# Sheet1.net
KiCad netlist of a schematic drawn in Altium Designer
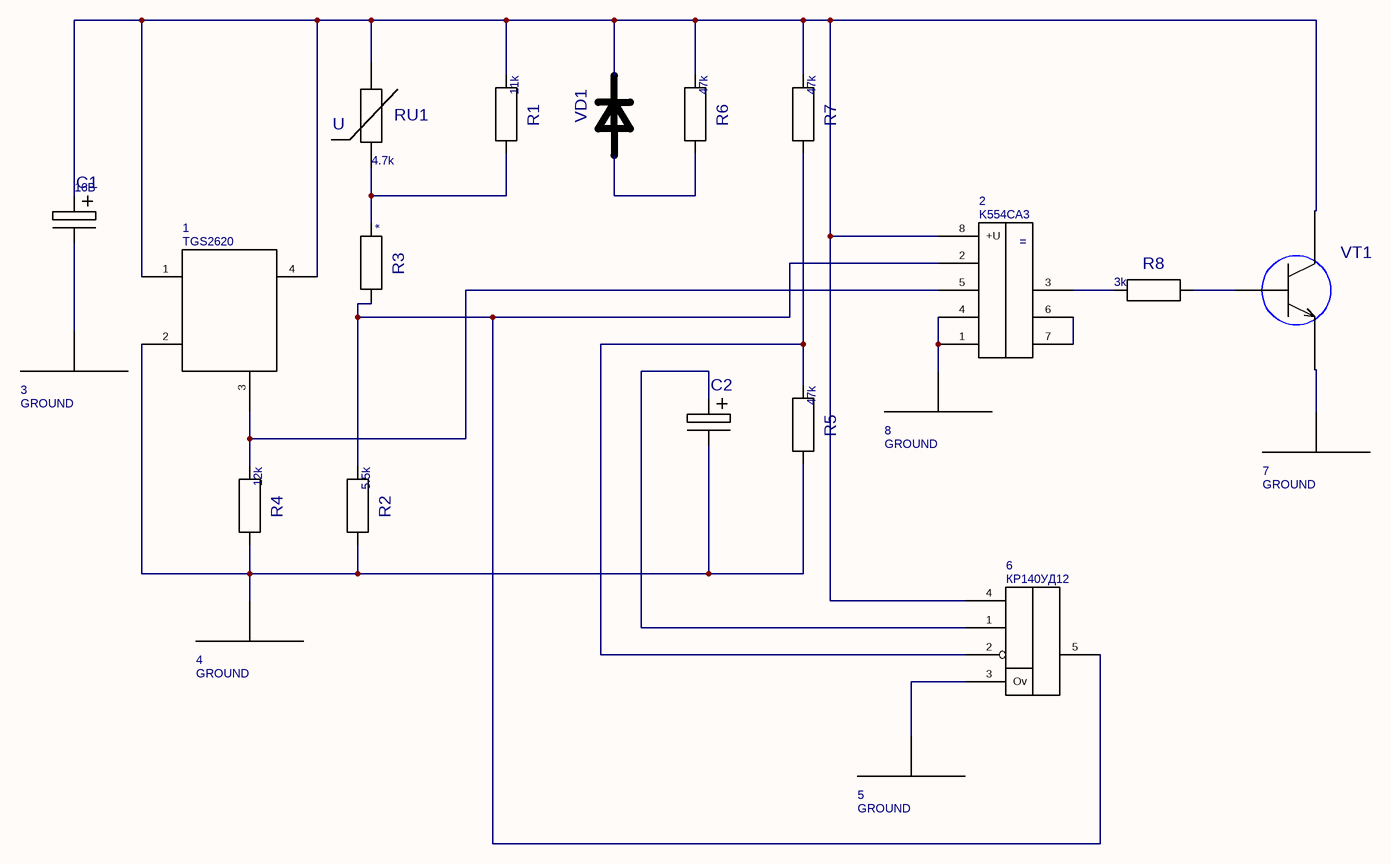
[diagram p0: Sheet1.SCHDOC]

(export (version "E")
  (design (tool "Eeschema 10.0.6"))
  (components
    (comp (ref "1") (value "TGS2620") (footprint "TGS2620") (libsource (lib "*") (part "TGS2620")))
    (comp (ref "2") (value "K554CA3") (footprint "K554CA3") (libsource (lib "*") (part "K554CA3")))
    (comp (ref "3") (value "GROUND") (footprint "GROUND") (libsource (lib "*") (part "GROUND")))
    (comp (ref "4") (value "GROUND") (footprint "GROUND") (libsource (lib "*") (part "GROUND")))
    (comp (ref "5") (value "GROUND") (footprint "GROUND") (libsource (lib "*") (part "GROUND")))
    (comp (ref "6") (value "КР140УД12") (footprint "КР140УД12") (libsource (lib "*") (part "КР140УД12")))
    (comp (ref "7") (value "GROUND") (footprint "GROUND") (libsource (lib "*") (part "GROUND")))
    (comp (ref "8") (value "GROUND") (footprint "GROUND") (libsource (lib "*") (part "GROUND")))
    (comp (ref "C1")
      (value "16B")
      (footprint "R50-35-08XX")
      (description "К50-35-1000МКФ-6,3В")
      (libsource (lib "*") (part "К50-35-1000МКФ-6,3В"))
    )
    (comp (ref "C2")
      (value "К50-35-220МКФ-10В-Г")
      (footprint "К50-35-0611-Г")
      (libsource (lib "*") (part "К50-35-220МКФ-10В-Г"))
    )
    (comp (ref "R1")
      (value "11k")
      (footprint "PR03(VISHAY)")
      (description "PR03(VISHAY)")
      (libsource (lib "*") (part "PR03(VISHAY)"))
    )
    (comp (ref "R2")
      (value "5.5k")
      (footprint "PR03(VISHAY)")
      (description "PR03(VISHAY)")
      (libsource (lib "*") (part "PR03(VISHAY)"))
    )
    (comp (ref "R3")
      (value "PR03(VISHAY)")
      (footprint "PR03(VISHAY)")
      (fields (field (name "ALTIUM_VALUE") "*"))
      (libsource (lib "*") (part "PR03(VISHAY)"))
    )
    (comp (ref "R4")
      (value "12k")
      (footprint "PR03(VISHAY)")
      (description "PR03(VISHAY)")
      (libsource (lib "*") (part "PR03(VISHAY)"))
    )
    (comp (ref "R5")
      (value "47k")
      (footprint "PR03(VISHAY)")
      (description "PR03(VISHAY)")
      (libsource (lib "*") (part "PR03(VISHAY)"))
    )
    (comp (ref "R6")
      (value "47k")
      (footprint "PR03(VISHAY)")
      (description "PR03(VISHAY)")
      (libsource (lib "*") (part "PR03(VISHAY)"))
    )
    (comp (ref "R7")
      (value "47k")
      (footprint "PR03(VISHAY)")
      (description "PR03(VISHAY)")
      (libsource (lib "*") (part "PR03(VISHAY)"))
    )
    (comp (ref "R8")
      (value "3k")
      (footprint "PR03(VISHAY)")
      (description "PR03(VISHAY)")
      (libsource (lib "*") (part "PR03(VISHAY)"))
    )
    (comp (ref "RU1")
      (value "4.7k")
      (footprint "S07K230")
      (description "SIOV-S07K300")
      (fields (field (name "AUTHOR") "pcbdesigner.ru"))
      (libsource (lib "*") (part "SIOV-S07K300"))
    )
    (comp (ref "VD1") (value "1N34") (footprint "DO-7") (libsource (lib "*") (part "1N34")))
    (comp (ref "VT1") (value "2N4401") (footprint "TO-92-1") (libsource (lib "*") (part "2N4401")))
  )
  (nets
    (net (code "1") (name "Net-(1-Pad2)") (class "Default")
      (node (ref "1") (pin "2") (pinfunction "2_2") (pintype "passive"))
      (node (ref "4") (pin "1") (pinfunction "1_1") (pintype "passive"))
      (node (ref "C2") (pin "2") (pinfunction "2_2") (pintype "passive"))
      (node (ref "R2") (pin "2") (pinfunction "2_2") (pintype "passive"))
      (node (ref "R4") (pin "2") (pinfunction "2_2") (pintype "passive"))
      (node (ref "R5") (pin "2") (pinfunction "2_2") (pintype "passive"))
    )
    (net (code "2") (name "Net-(1-Pad3)") (class "Default")
      (node (ref "1") (pin "3") (pinfunction "3_3") (pintype "passive"))
      (node (ref "2") (pin "5") (pintype "passive"))
      (node (ref "R4") (pin "1") (pinfunction "1_1") (pintype "passive"))
    )
    (net (code "3") (name "Net-(2-+U)") (class "Default")
      (node (ref "1") (pin "1") (pinfunction "1_1") (pintype "passive"))
      (node (ref "1") (pin "4") (pinfunction "4_4") (pintype "passive"))
      (node (ref "2") (pin "8") (pinfunction "+U_8") (pintype "passive"))
      (node (ref "6") (pin "4") (pintype "passive"))
      (node (ref "C1") (pin "1") (pinfunction "1_1") (pintype "passive"))
      (node (ref "R1") (pin "1") (pinfunction "1_1") (pintype "passive"))
      (node (ref "R6") (pin "1") (pinfunction "1_1") (pintype "passive"))
      (node (ref "R7") (pin "1") (pinfunction "1_1") (pintype "passive"))
      (node (ref "RU1") (pin "2") (pinfunction "2_2") (pintype "passive"))
      (node (ref "VD1") (pin "K") (pinfunction "K_K") (pintype "passive"))
      (node (ref "VT1") (pin "3") (pinfunction "K_3") (pintype "passive"))
    )
    (net (code "4") (name "Net-(2-Ov)") (class "Default")
      (node (ref "2") (pin "1") (pintype "passive"))
      (node (ref "2") (pin "4") (pinfunction "Ov_4") (pintype "passive"))
      (node (ref "8") (pin "1") (pinfunction "1_1") (pintype "passive"))
    )
    (net (code "5") (name "Net-(2-Pad3)") (class "Default")
      (node (ref "2") (pin "3") (pintype "passive"))
      (node (ref "R8") (pin "1") (pinfunction "1_1") (pintype "passive"))
    )
    (net (code "6") (name "Net-(2-Pad6)") (class "Default")
      (node (ref "2") (pin "6") (pintype "passive"))
      (node (ref "2") (pin "7") (pintype "passive"))
    )
    (net (code "7") (name "Net-(3-Pad1)") (class "Default")
      (node (ref "3") (pin "1") (pinfunction "1_1") (pintype "passive"))
      (node (ref "C1") (pin "2") (pinfunction "2_2") (pintype "passive"))
    )
    (net (code "8") (name "Net-(6-+U)") (class "Default")
      (node (ref "2") (pin "2") (pintype "passive"))
      (node (ref "6") (pin "5") (pinfunction "+U_5") (pintype "passive"))
      (node (ref "R2") (pin "1") (pinfunction "1_1") (pintype "passive"))
      (node (ref "R3") (pin "2") (pinfunction "2_2") (pintype "passive"))
    )
    (net (code "9") (name "Net-(6-Ov)") (class "Default")
      (node (ref "5") (pin "1") (pinfunction "1_1") (pintype "passive"))
      (node (ref "6") (pin "3") (pinfunction "Ov_3") (pintype "passive"))
    )
    (net (code "10") (name "Net-(6-Pad1)") (class "Default")
      (node (ref "6") (pin "1") (pintype "passive"))
      (node (ref "C2") (pin "1") (pinfunction "1_1") (pintype "passive"))
    )
    (net (code "11") (name "Net-(6-Pad2)") (class "Default")
      (node (ref "6") (pin "2") (pintype "passive"))
      (node (ref "R5") (pin "1") (pinfunction "1_1") (pintype "passive"))
      (node (ref "R7") (pin "2") (pinfunction "2_2") (pintype "passive"))
    )
    (net (code "12") (name "Net-(R1-Pad2)") (class "Default")
      (node (ref "R1") (pin "2") (pinfunction "2_2") (pintype "passive"))
      (node (ref "R3") (pin "1") (pinfunction "1_1") (pintype "passive"))
      (node (ref "RU1") (pin "1") (pinfunction "1_1") (pintype "passive"))
    )
    (net (code "13") (name "Net-(R6-Pad2)") (class "Default")
      (node (ref "R6") (pin "2") (pinfunction "2_2") (pintype "passive"))
      (node (ref "VD1") (pin "A") (pinfunction "A_A") (pintype "passive"))
    )
    (net (code "14") (name "Net-(VT1-B)") (class "Default")
      (node (ref "R8") (pin "2") (pinfunction "2_2") (pintype "passive"))
      (node (ref "VT1") (pin "2") (pinfunction "B_2") (pintype "passive"))
    )
    (net (code "15") (name "Net-(VT1-E)") (class "Default")
      (node (ref "7") (pin "1") (pinfunction "1_1") (pintype "passive"))
      (node (ref "VT1") (pin "1") (pinfunction "E_1") (pintype "passive"))
    )
  )
)
